# SCH_inf3-lab2_2022-05-08.net
KiCad netlist of a schematic drawn in EasyEDA
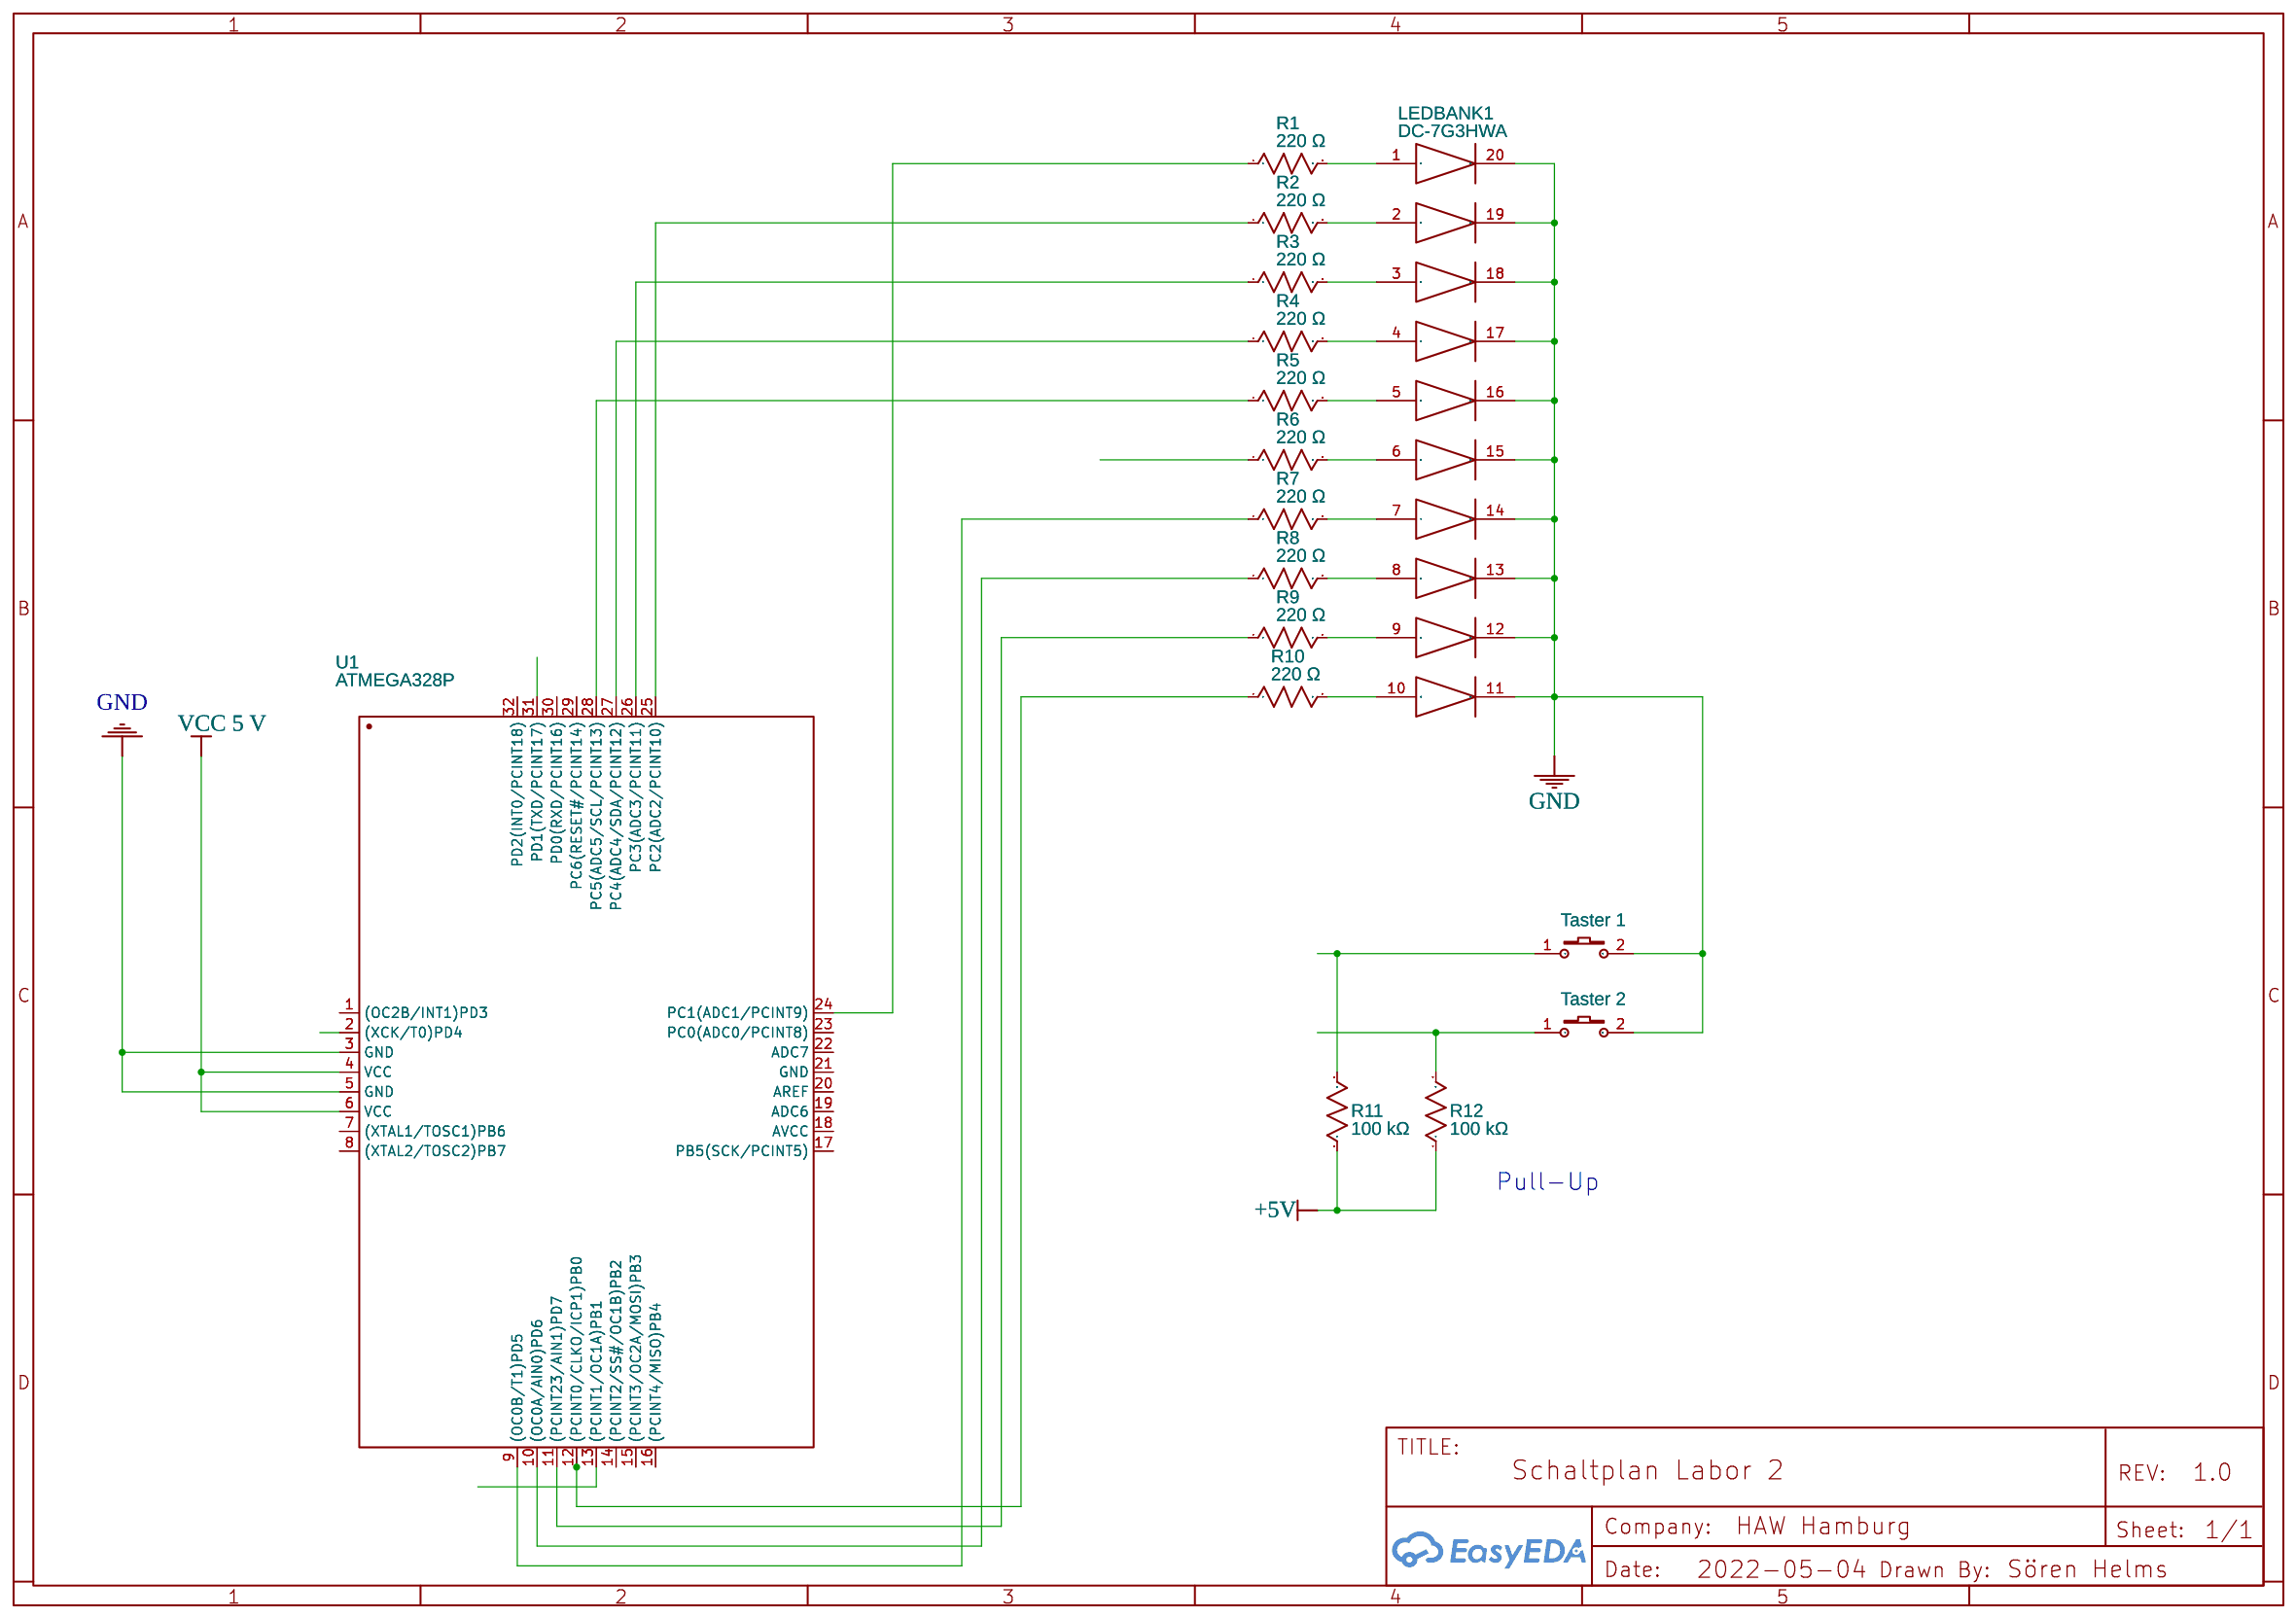
[diagram p0: schematic sheet]

(export (version "E")
  (design (tool "Eeschema 10.0.6"))
  (components
    (comp (ref "KEY1")
      (value "Taster 1")
      (fields
        (field (name "BOM_Manufacturer Part") "K2-1107ST-A4SW-06")
        (field (name "BOM_Supplier Part") "C118141")
      )
      (libsource (lib "") (part "K2-3.6×6.1_SMD"))
    )
    (comp (ref "KEY2")
      (value "Taster 2")
      (fields
        (field (name "BOM_Manufacturer Part") "K2-1107ST-A4SW-06")
        (field (name "BOM_Supplier Part") "C118141")
      )
      (libsource (lib "") (part "K2-3.6×6.1_SMD"))
    )
    (comp (ref "LEDBANK1")
      (value "DC-7G3HWA")
      (fields (field (name "BOM_Supplier Part") "undefined"))
      (libsource (lib "") (part "DC-7G3HWA"))
    )
    (comp (ref "R1") (value "220 Ω") (libsource (lib "") (part "R_0603_US")))
    (comp (ref "R2") (value "220 Ω") (libsource (lib "") (part "R_0603_US")))
    (comp (ref "R3") (value "220 Ω") (libsource (lib "") (part "R_0603_US")))
    (comp (ref "R4") (value "220 Ω") (libsource (lib "") (part "R_0603_US")))
    (comp (ref "R5") (value "220 Ω") (libsource (lib "") (part "R_0603_US")))
    (comp (ref "R6") (value "220 Ω") (libsource (lib "") (part "R_0603_US")))
    (comp (ref "R7") (value "220 Ω") (libsource (lib "") (part "R_0603_US")))
    (comp (ref "R8") (value "220 Ω") (libsource (lib "") (part "R_0603_US")))
    (comp (ref "R9") (value "220 Ω") (libsource (lib "") (part "R_0603_US")))
    (comp (ref "R10") (value "220 Ω") (libsource (lib "") (part "R_0603_US")))
    (comp (ref "R11") (value "100 kΩ") (libsource (lib "") (part "R_0603_US_1")))
    (comp (ref "R12") (value "100 kΩ") (libsource (lib "") (part "R_0603_US_1")))
    (comp (ref "U1")
      (value "ATMEGA328P")
      (fields
        (field (name "BOM_Manufacturer Part") "ATmega328P")
        (field (name "BOM_Supplier Part") "C9900009806")
      )
      (libsource (lib "") (part "ATMEGA328P"))
    )
  )
  (nets
    (net (code "1") (name "+5V") (class "Default")
      (node (ref "R11") (pin "1") (pinfunction "1_1") (pintype "unspecified"))
      (node (ref "R12") (pin "1") (pinfunction "1_1") (pintype "unspecified"))
    )
    (net (code "2") (name "GND") (class "Default")
      (node (ref "KEY1") (pin "2") (pinfunction "2_2") (pintype "unspecified"))
      (node (ref "KEY2") (pin "2") (pinfunction "2_2") (pintype "unspecified"))
      (node (ref "LEDBANK1") (pin "11") (pinfunction "11_11") (pintype "unspecified"))
      (node (ref "LEDBANK1") (pin "12") (pinfunction "12_12") (pintype "unspecified"))
      (node (ref "LEDBANK1") (pin "13") (pinfunction "13_13") (pintype "unspecified"))
      (node (ref "LEDBANK1") (pin "14") (pinfunction "14_14") (pintype "unspecified"))
      (node (ref "LEDBANK1") (pin "15") (pinfunction "15_15") (pintype "unspecified"))
      (node (ref "LEDBANK1") (pin "16") (pinfunction "16_16") (pintype "unspecified"))
      (node (ref "LEDBANK1") (pin "17") (pinfunction "17_17") (pintype "unspecified"))
      (node (ref "LEDBANK1") (pin "18") (pinfunction "18_18") (pintype "unspecified"))
      (node (ref "LEDBANK1") (pin "19") (pinfunction "19_19") (pintype "unspecified"))
      (node (ref "LEDBANK1") (pin "20") (pinfunction "20_20") (pintype "unspecified"))
      (node (ref "U1") (pin "3") (pinfunction "GND_3") (pintype "unspecified"))
      (node (ref "U1") (pin "5") (pinfunction "GND_5") (pintype "unspecified"))
    )
    (net (code "3") (name "Net-(KEY1-Pad1)") (class "Default")
      (node (ref "KEY1") (pin "1") (pinfunction "1_1") (pintype "unspecified"))
      (node (ref "R11") (pin "2") (pinfunction "2_2") (pintype "unspecified"))
    )
    (net (code "4") (name "Net-(KEY2-Pad1)") (class "Default")
      (node (ref "KEY2") (pin "1") (pinfunction "1_1") (pintype "unspecified"))
      (node (ref "R12") (pin "2") (pinfunction "2_2") (pintype "unspecified"))
    )
    (net (code "5") (name "Net-(LEDBANK1-21)") (class "Default")
      (node (ref "LEDBANK1") (pin "5") (pinfunction "21_5") (pintype "unspecified"))
      (node (ref "R5") (pin "2") (pinfunction "2_2") (pintype "unspecified"))
    )
    (net (code "6") (name "Net-(LEDBANK1-Pad1)") (class "Default")
      (node (ref "LEDBANK1") (pin "1") (pinfunction "1_1") (pintype "unspecified"))
      (node (ref "R1") (pin "2") (pinfunction "2_2") (pintype "unspecified"))
    )
    (net (code "7") (name "Net-(LEDBANK1-Pad2)") (class "Default")
      (node (ref "LEDBANK1") (pin "2") (pinfunction "2_2") (pintype "unspecified"))
      (node (ref "R2") (pin "2") (pinfunction "2_2") (pintype "unspecified"))
    )
    (net (code "8") (name "Net-(LEDBANK1-Pad3)") (class "Default")
      (node (ref "LEDBANK1") (pin "3") (pinfunction "3_3") (pintype "unspecified"))
      (node (ref "R3") (pin "2") (pinfunction "2_2") (pintype "unspecified"))
    )
    (net (code "9") (name "Net-(LEDBANK1-Pad4)") (class "Default")
      (node (ref "LEDBANK1") (pin "4") (pinfunction "4_4") (pintype "unspecified"))
      (node (ref "R4") (pin "2") (pinfunction "2_2") (pintype "unspecified"))
    )
    (net (code "10") (name "Net-(LEDBANK1-Pad6)") (class "Default")
      (node (ref "LEDBANK1") (pin "6") (pinfunction "6_6") (pintype "unspecified"))
      (node (ref "R6") (pin "2") (pinfunction "2_2") (pintype "unspecified"))
    )
    (net (code "11") (name "Net-(LEDBANK1-Pad7)") (class "Default")
      (node (ref "LEDBANK1") (pin "7") (pinfunction "7_7") (pintype "unspecified"))
      (node (ref "R7") (pin "2") (pinfunction "2_2") (pintype "unspecified"))
    )
    (net (code "12") (name "Net-(LEDBANK1-Pad8)") (class "Default")
      (node (ref "LEDBANK1") (pin "8") (pinfunction "8_8") (pintype "unspecified"))
      (node (ref "R8") (pin "2") (pinfunction "2_2") (pintype "unspecified"))
    )
    (net (code "13") (name "Net-(LEDBANK1-Pad9)") (class "Default")
      (node (ref "LEDBANK1") (pin "9") (pinfunction "9_9") (pintype "unspecified"))
      (node (ref "R9") (pin "2") (pinfunction "2_2") (pintype "unspecified"))
    )
    (net (code "14") (name "Net-(LEDBANK1-Pad10)") (class "Default")
      (node (ref "LEDBANK1") (pin "10") (pinfunction "10_10") (pintype "unspecified"))
      (node (ref "R10") (pin "2") (pinfunction "2_2") (pintype "unspecified"))
    )
    (net (code "15") (name "Net-(U1-(OC0A{slash}AIN0)PD6)") (class "Default")
      (node (ref "R8") (pin "1") (pinfunction "1_1") (pintype "unspecified"))
      (node (ref "U1") (pin "10") (pinfunction "(OC0A/AIN0)PD6_10") (pintype "unspecified"))
    )
    (net (code "16") (name "Net-(U1-(OC0B{slash}T1)PD5)") (class "Default")
      (node (ref "R7") (pin "1") (pinfunction "1_1") (pintype "unspecified"))
      (node (ref "U1") (pin "9") (pinfunction "(OC0B/T1)PD5_9") (pintype "unspecified"))
    )
    (net (code "17") (name "Net-(U1-(PCINT0{slash}CLKO{slash}ICP1)PB0)") (class "Default")
      (node (ref "R10") (pin "1") (pinfunction "1_1") (pintype "unspecified"))
      (node (ref "U1") (pin "12") (pinfunction "(PCINT0/CLKO/ICP1)PB0_12") (pintype "unspecified"))
    )
    (net (code "18") (name "Net-(U1-(PCINT23{slash}AIN1)PD7)") (class "Default")
      (node (ref "R9") (pin "1") (pinfunction "1_1") (pintype "unspecified"))
      (node (ref "U1") (pin "11") (pinfunction "(PCINT23/AIN1)PD7_11") (pintype "unspecified"))
    )
    (net (code "19") (name "Net-(U1-PC1(ADC1{slash}PCINT9))") (class "Default")
      (node (ref "R1") (pin "1") (pinfunction "1_1") (pintype "unspecified"))
      (node (ref "U1") (pin "24") (pinfunction "PC1(ADC1/PCINT9)_24") (pintype "unspecified"))
    )
    (net (code "20") (name "Net-(U1-PC2(ADC2{slash}PCINT10))") (class "Default")
      (node (ref "R2") (pin "1") (pinfunction "1_1") (pintype "unspecified"))
      (node (ref "U1") (pin "25") (pinfunction "PC2(ADC2/PCINT10)_25") (pintype "unspecified"))
    )
    (net (code "21") (name "Net-(U1-PC3(ADC3{slash}PCINT11))") (class "Default")
      (node (ref "R3") (pin "1") (pinfunction "1_1") (pintype "unspecified"))
      (node (ref "U1") (pin "26") (pinfunction "PC3(ADC3/PCINT11)_26") (pintype "unspecified"))
    )
    (net (code "22") (name "Net-(U1-PC4(ADC4{slash}SDA{slash}PCINT12))") (class "Default")
      (node (ref "R4") (pin "1") (pinfunction "1_1") (pintype "unspecified"))
      (node (ref "U1") (pin "27") (pinfunction "PC4(ADC4/SDA/PCINT12)_27") (pintype "unspecified"))
    )
    (net (code "23") (name "Net-(U1-PC5(ADC5{slash}SCL{slash}PCINT13))") (class "Default")
      (node (ref "R5") (pin "1") (pinfunction "1_1") (pintype "unspecified"))
      (node (ref "U1") (pin "28") (pinfunction "PC5(ADC5/SCL/PCINT13)_28") (pintype "unspecified"))
    )
    (net (code "24") (name "VCC 5 V") (class "Default")
      (node (ref "U1") (pin "4") (pinfunction "VCC_4") (pintype "unspecified"))
      (node (ref "U1") (pin "6") (pinfunction "VCC_6") (pintype "unspecified"))
    )
    (net (code "25") (name "unconnected-(R6-Pad1)") (class "Default")
      (node (ref "R6") (pin "1") (pinfunction "1_1") (pintype "unspecified"))
    )
    (net (code "26") (name "unconnected-(U1-(OC2B{slash}INT1)PD3-Pad1)") (class "Default")
      (node (ref "U1") (pin "1") (pinfunction "(OC2B/INT1)PD3_1") (pintype "unspecified"))
    )
    (net (code "27") (name "unconnected-(U1-(PCINT1{slash}OC1A)PB1-Pad13)") (class "Default")
      (node (ref "U1") (pin "13") (pinfunction "(PCINT1/OC1A)PB1_13") (pintype "unspecified"))
    )
    (net (code "28") (name "unconnected-(U1-(PCINT2{slash}SS#{slash}OC1B)PB2-Pad14)") (class "Default")
      (node (ref "U1") (pin "14") (pinfunction "(PCINT2/SS#/OC1B)PB2_14") (pintype "unspecified"))
    )
    (net (code "29") (name "unconnected-(U1-(PCINT3{slash}OC2A{slash}MOSI)PB3-Pad15)") (class "Default")
      (node (ref "U1") (pin "15") (pinfunction "(PCINT3/OC2A/MOSI)PB3_15") (pintype "unspecified"))
    )
    (net (code "30") (name "unconnected-(U1-(PCINT4{slash}MISO)PB4-Pad16)") (class "Default")
      (node (ref "U1") (pin "16") (pinfunction "(PCINT4/MISO)PB4_16") (pintype "unspecified"))
    )
    (net (code "31") (name "unconnected-(U1-(XCK{slash}T0)PD4-Pad2)") (class "Default")
      (node (ref "U1") (pin "2") (pinfunction "(XCK/T0)PD4_2") (pintype "unspecified"))
    )
    (net (code "32") (name "unconnected-(U1-(XTAL1{slash}TOSC1)PB6-Pad7)") (class "Default")
      (node (ref "U1") (pin "7") (pinfunction "(XTAL1/TOSC1)PB6_7") (pintype "unspecified"))
    )
    (net (code "33") (name "unconnected-(U1-(XTAL2{slash}TOSC2)PB7-Pad8)") (class "Default")
      (node (ref "U1") (pin "8") (pinfunction "(XTAL2/TOSC2)PB7_8") (pintype "unspecified"))
    )
    (net (code "34") (name "unconnected-(U1-ADC6-Pad19)") (class "Default")
      (node (ref "U1") (pin "19") (pinfunction "ADC6_19") (pintype "unspecified"))
    )
    (net (code "35") (name "unconnected-(U1-ADC7-Pad22)") (class "Default")
      (node (ref "U1") (pin "22") (pinfunction "ADC7_22") (pintype "unspecified"))
    )
    (net (code "36") (name "unconnected-(U1-AREF-Pad20)") (class "Default")
      (node (ref "U1") (pin "20") (pinfunction "AREF_20") (pintype "unspecified"))
    )
    (net (code "37") (name "unconnected-(U1-AVCC-Pad18)") (class "Default")
      (node (ref "U1") (pin "18") (pinfunction "AVCC_18") (pintype "unspecified"))
    )
    (net (code "38") (name "unconnected-(U1-GND-Pad21)") (class "Default")
      (node (ref "U1") (pin "21") (pinfunction "GND_21") (pintype "unspecified"))
    )
    (net (code "39") (name "unconnected-(U1-PB5(SCK{slash}PCINT5)-Pad17)") (class "Default")
      (node (ref "U1") (pin "17") (pinfunction "PB5(SCK/PCINT5)_17") (pintype "unspecified"))
    )
    (net (code "40") (name "unconnected-(U1-PC0(ADC0{slash}PCINT8)-Pad23)") (class "Default")
      (node (ref "U1") (pin "23") (pinfunction "PC0(ADC0/PCINT8)_23") (pintype "unspecified"))
    )
    (net (code "41") (name "unconnected-(U1-PC6(RESET#{slash}PCINT14)-Pad29)") (class "Default")
      (node (ref "U1") (pin "29") (pinfunction "PC6(RESET#/PCINT14)_29") (pintype "unspecified"))
    )
    (net (code "42") (name "unconnected-(U1-PD0(RXD{slash}PCINT16)-Pad30)") (class "Default")
      (node (ref "U1") (pin "30") (pinfunction "PD0(RXD/PCINT16)_30") (pintype "unspecified"))
    )
    (net (code "43") (name "unconnected-(U1-PD1(TXD{slash}PCINT17)-Pad31)") (class "Default")
      (node (ref "U1") (pin "31") (pinfunction "PD1(TXD/PCINT17)_31") (pintype "unspecified"))
    )
    (net (code "44") (name "unconnected-(U1-PD2(INT0{slash}PCINT18)-Pad32)") (class "Default")
      (node (ref "U1") (pin "32") (pinfunction "PD2(INT0/PCINT18)_32") (pintype "unspecified"))
    )
  )
)
